# PID.net
KiCad netlist of a schematic drawn in EasyEDA Pro
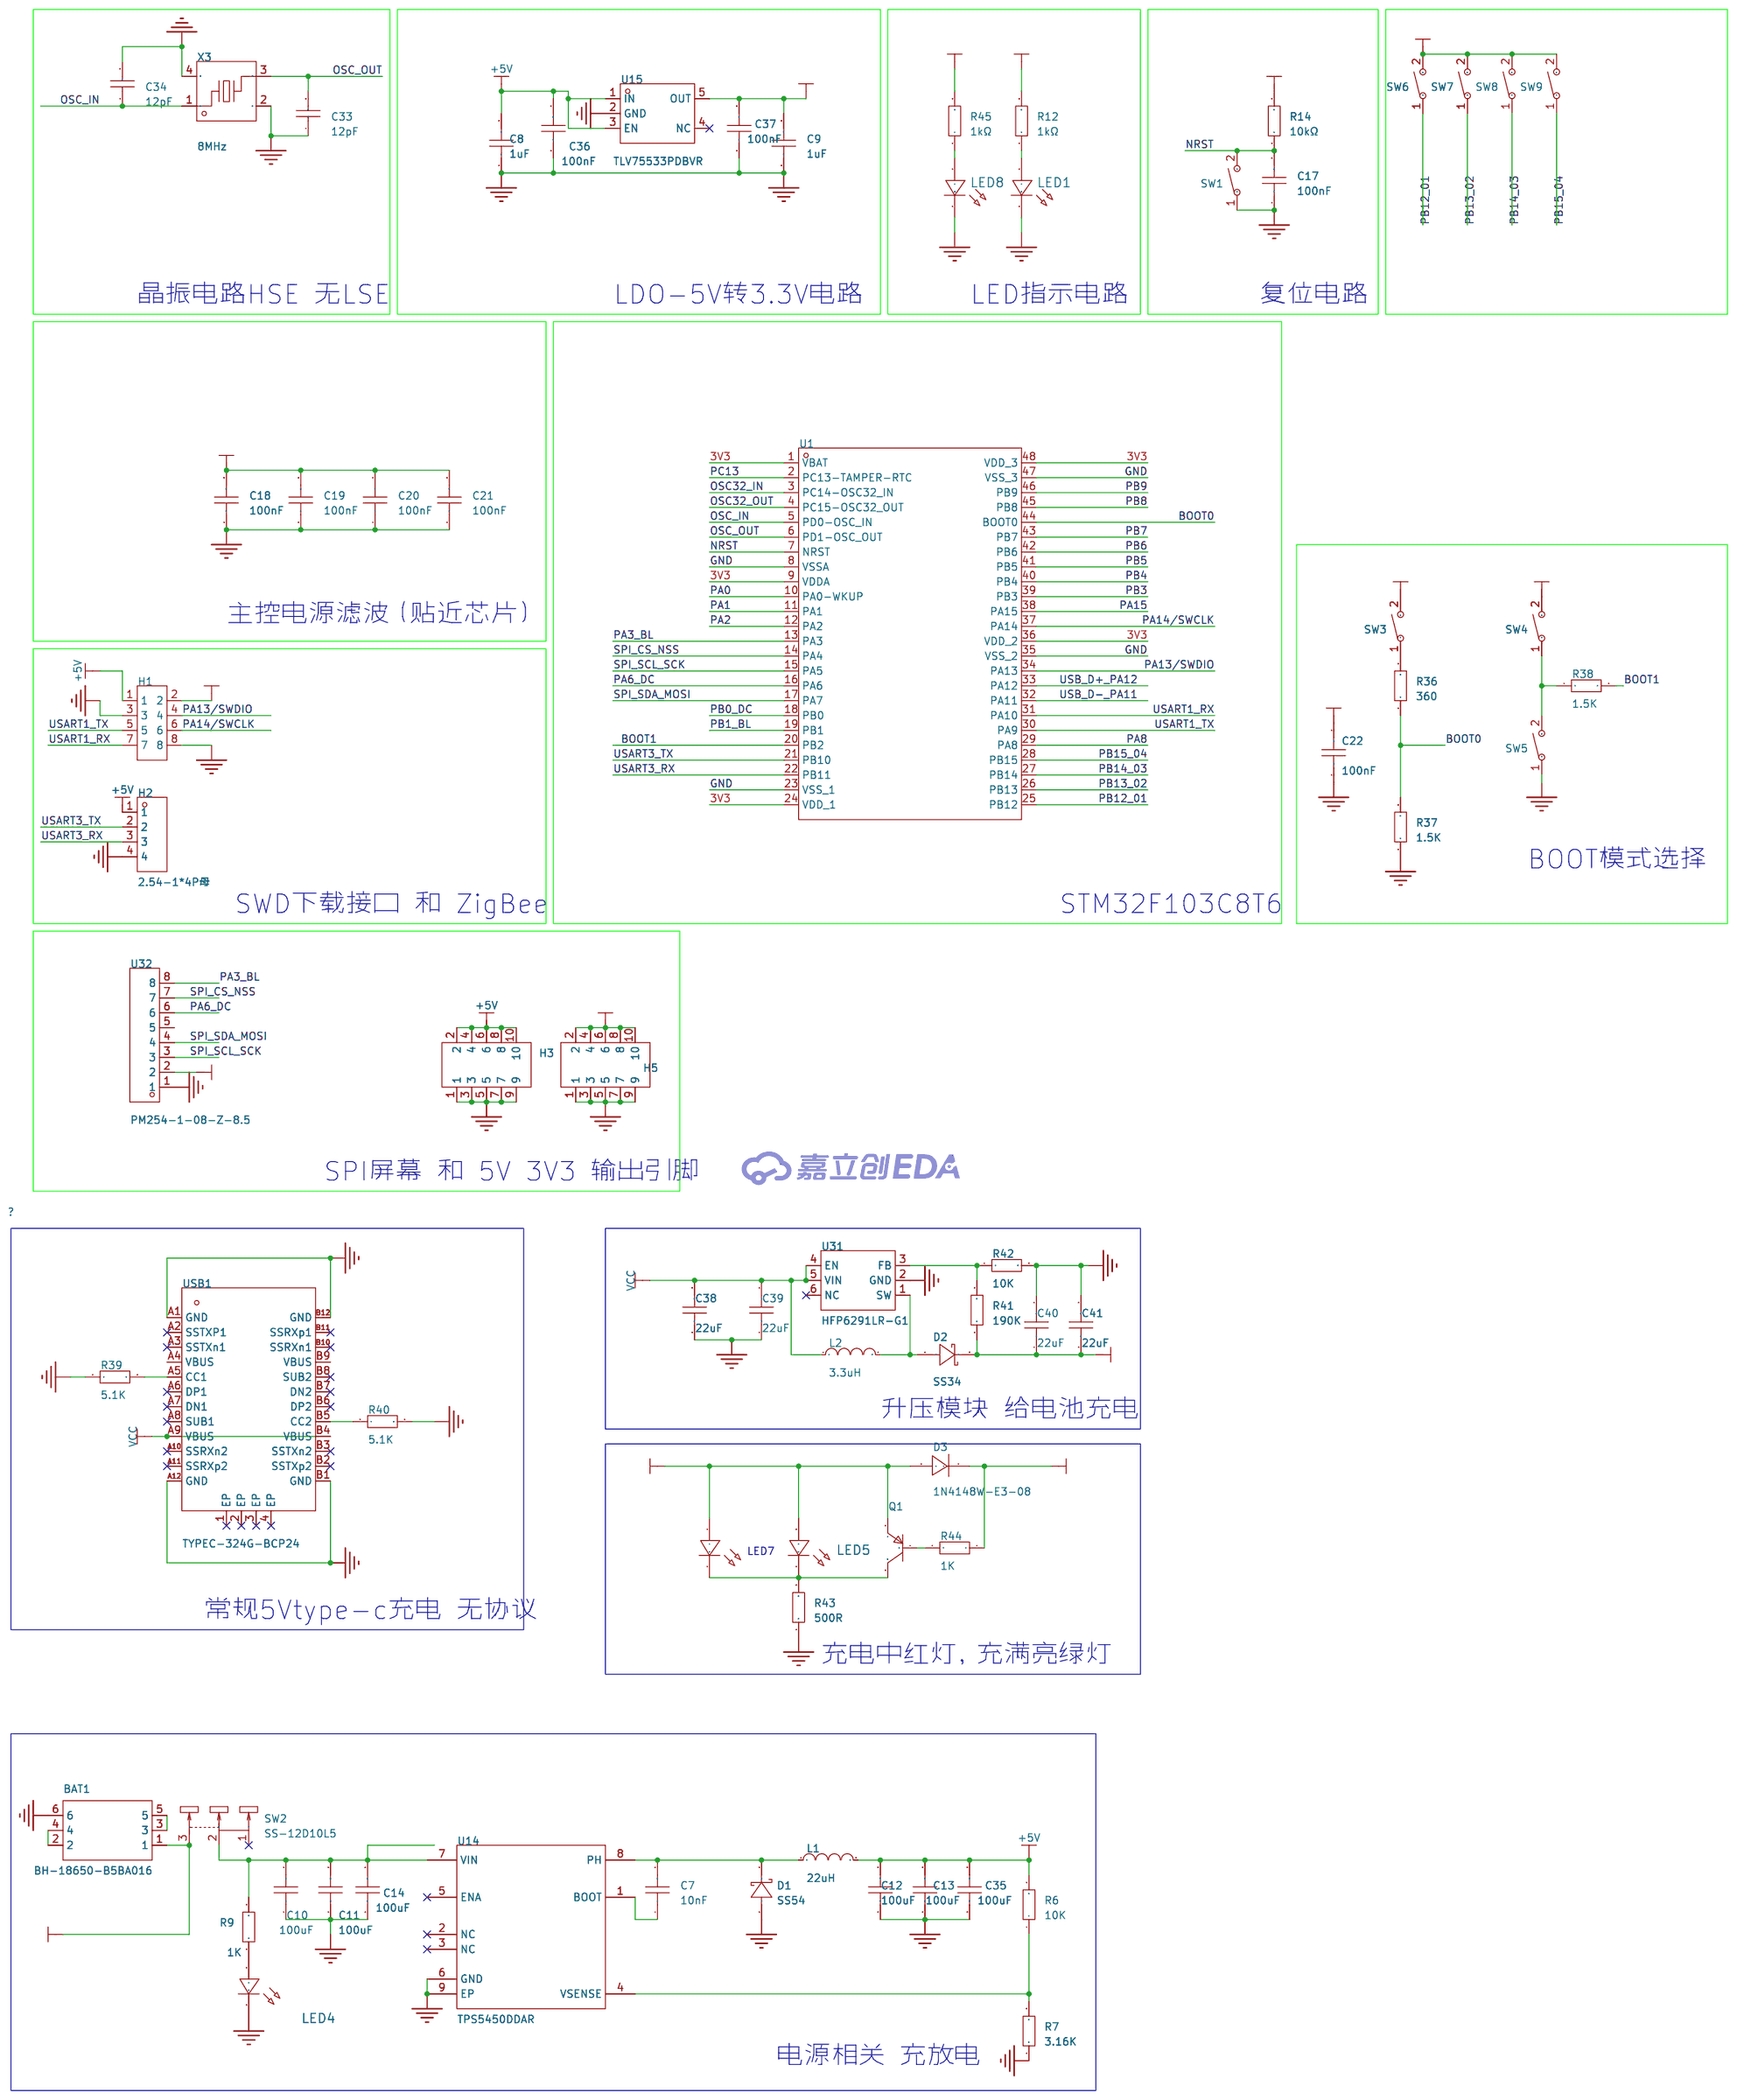
[diagram p0: schematic sheet]

(export (version "E")
  (design (tool "Eeschema 10.0.6"))
  (components
    (comp (ref "BAT1")
      (value "BH-18650-B5BA016")
      (footprint "easyedapro:BAT-SMD_BH-18650-B5BA016")
      (description "连接器类型:电池盒;适用电池规格:-;触点电镀:金;工作温度范围:-25°C~+85°C;")
      (fields (field (name "Manufacturer") "MYOUNG(美阳)"))
      (libsource (lib "easyedapro") (part "BH-18650-B5BA016"))
    )
    (comp (ref "C7")
      (value "100nF")
      (footprint "easyedapro:C0603")
      (libsource (lib "easyedapro") (part "CapAcitance"))
    )
    (comp (ref "C8")
      (value "100nF")
      (footprint "easyedapro:C0603")
      (libsource (lib "easyedapro") (part "CapAcitance"))
    )
    (comp (ref "C9")
      (value "100nF")
      (footprint "easyedapro:C0603")
      (libsource (lib "easyedapro") (part "CapAcitance"))
    )
    (comp (ref "C10")
      (value "100uF")
      (footprint "easyedapro:C1206")
      (description "容值:100uF;精度:±20%;额定电压:10V;材质(温度系数):X5R;")
      (fields
        (field (name "Manufacturer Part") "HGC1206R5107M100NSPJ")
        (field (name "Manufacturer") "Chinocera(华瓷)")
      )
      (libsource (lib "easyedapro") (part "HGC1206R5107M100NSPJ"))
    )
    (comp (ref "C11")
      (value "100uF")
      (footprint "easyedapro:C1206")
      (description "容值:100uF;精度:±20%;额定电压:10V;材质(温度系数):X5R;")
      (fields
        (field (name "Manufacturer Part") "HGC1206R5107M100NSPJ")
        (field (name "Manufacturer") "Chinocera(华瓷)")
      )
      (libsource (lib "easyedapro") (part "HGC1206R5107M100NSPJ"))
    )
    (comp (ref "C12")
      (value "100uF")
      (footprint "easyedapro:C1206")
      (description "容值:100uF;精度:±20%;额定电压:10V;材质(温度系数):X5R;")
      (fields
        (field (name "Manufacturer Part") "HGC1206R5107M100NSPJ")
        (field (name "Manufacturer") "Chinocera(华瓷)")
      )
      (libsource (lib "easyedapro") (part "HGC1206R5107M100NSPJ"))
    )
    (comp (ref "C13")
      (value "100uF")
      (footprint "easyedapro:C1206")
      (description "容值:100uF;精度:±20%;额定电压:10V;材质(温度系数):X5R;")
      (fields
        (field (name "Manufacturer Part") "HGC1206R5107M100NSPJ")
        (field (name "Manufacturer") "Chinocera(华瓷)")
      )
      (libsource (lib "easyedapro") (part "HGC1206R5107M100NSPJ"))
    )
    (comp (ref "C14")
      (value "100uF")
      (footprint "easyedapro:C1206")
      (description "容值:100uF;精度:±20%;额定电压:10V;材质(温度系数):X5R;")
      (fields
        (field (name "Manufacturer Part") "HGC1206R5107M100NSPJ")
        (field (name "Manufacturer") "Chinocera(华瓷)")
      )
      (libsource (lib "easyedapro") (part "HGC1206R5107M100NSPJ"))
    )
    (comp (ref "C17")
      (value "100nF")
      (footprint "easyedapro:C0402")
      (description "容值:100nF;精度:±10%;额定电压:50V;材质(温度系数):X7R;")
      (fields
        (field (name "Manufacturer Part") "GRM155R71H104KE14D")
        (field (name "Manufacturer") "muRata(村田)")
      )
      (libsource (lib "easyedapro") (part "GRM155R71H104KE14D"))
    )
    (comp (ref "C18")
      (value "100nF")
      (footprint "easyedapro:C0402")
      (description "容值:100nF;精度:±10%;额定电压:50V;材质(温度系数):X7R;")
      (fields
        (field (name "Manufacturer Part") "GRM155R71H104KE14D")
        (field (name "Manufacturer") "muRata(村田)")
      )
      (libsource (lib "easyedapro") (part "GRM155R71H104KE14D"))
    )
    (comp (ref "C19")
      (value "100nF")
      (footprint "easyedapro:C0402")
      (description "容值:100nF;精度:±10%;额定电压:50V;材质(温度系数):X7R;")
      (fields
        (field (name "Manufacturer Part") "GRM155R71H104KE14D")
        (field (name "Manufacturer") "muRata(村田)")
      )
      (libsource (lib "easyedapro") (part "GRM155R71H104KE14D"))
    )
    (comp (ref "C20")
      (value "100nF")
      (footprint "easyedapro:C0402")
      (description "容值:100nF;精度:±10%;额定电压:50V;材质(温度系数):X7R;")
      (fields
        (field (name "Manufacturer Part") "GRM155R71H104KE14D")
        (field (name "Manufacturer") "muRata(村田)")
      )
      (libsource (lib "easyedapro") (part "GRM155R71H104KE14D"))
    )
    (comp (ref "C21")
      (value "100nF")
      (footprint "easyedapro:C0402")
      (description "容值:100nF;精度:±10%;额定电压:50V;材质(温度系数):X7R;")
      (fields
        (field (name "Manufacturer Part") "GRM155R71H104KE14D")
        (field (name "Manufacturer") "muRata(村田)")
      )
      (libsource (lib "easyedapro") (part "GRM155R71H104KE14D"))
    )
    (comp (ref "C22")
      (value "100nF")
      (footprint "easyedapro:C0402")
      (description "容值:100nF;精度:±10%;额定电压:50V;材质(温度系数):X7R;")
      (fields
        (field (name "Manufacturer Part") "GRM155R71H104KE14D")
        (field (name "Manufacturer") "muRata(村田)")
      )
      (libsource (lib "easyedapro") (part "GRM155R71H104KE14D"))
    )
    (comp (ref "C33")
      (value "12pF")
      (footprint "easyedapro:C0402")
      (description "容值:12pF;精度:±5%;额定电压:50V;材质(温度系数):C0G;")
      (fields (field (name "Manufacturer Part") "0402CG120J500NT") (field (name "Manufacturer") "FH(风华)"))
      (libsource (lib "easyedapro") (part "0402CG120J500NT"))
    )
    (comp (ref "C34")
      (value "12pF")
      (footprint "easyedapro:C0402")
      (description "容值:12pF;精度:±5%;额定电压:50V;材质(温度系数):C0G;")
      (fields (field (name "Manufacturer Part") "0402CG120J500NT") (field (name "Manufacturer") "FH(风华)"))
      (libsource (lib "easyedapro") (part "0402CG120J500NT"))
    )
    (comp (ref "C35")
      (value "100uF")
      (footprint "easyedapro:C1206")
      (description "容值:100uF;精度:±20%;额定电压:10V;材质(温度系数):X5R;")
      (fields
        (field (name "Manufacturer Part") "HGC1206R5107M100NSPJ")
        (field (name "Manufacturer") "Chinocera(华瓷)")
      )
      (libsource (lib "easyedapro") (part "HGC1206R5107M100NSPJ"))
    )
    (comp (ref "C36")
      (value "100nF")
      (footprint "easyedapro:C0402")
      (description "容值:100nF;精度:±10%;额定电压:50V;材质(温度系数):X7R;")
      (fields
        (field (name "Manufacturer Part") "GRM155R71H104KE14D")
        (field (name "Manufacturer") "muRata(村田)")
      )
      (libsource (lib "easyedapro") (part "GRM155R71H104KE14D"))
    )
    (comp (ref "C37")
      (value "100nF")
      (footprint "easyedapro:C0402")
      (description "容值:100nF;精度:±10%;额定电压:50V;材质(温度系数):X7R;")
      (fields
        (field (name "Manufacturer Part") "GRM155R71H104KE14D")
        (field (name "Manufacturer") "muRata(村田)")
      )
      (libsource (lib "easyedapro") (part "GRM155R71H104KE14D"))
    )
    (comp (ref "C38")
      (value "22uF")
      (footprint "easyedapro:C0603")
      (libsource (lib "easyedapro") (part "CapAcitance"))
    )
    (comp (ref "C39")
      (value "22uF")
      (footprint "easyedapro:C0603")
      (libsource (lib "easyedapro") (part "CapAcitance"))
    )
    (comp (ref "C40")
      (value "22uF")
      (footprint "easyedapro:C0603")
      (libsource (lib "easyedapro") (part "CapAcitance"))
    )
    (comp (ref "C41")
      (value "22uF")
      (footprint "easyedapro:C0603")
      (libsource (lib "easyedapro") (part "CapAcitance"))
    )
    (comp (ref "D1")
      (value "SS54")
      (footprint "easyedapro:SMA_L4.3-W2.6-LS5.0-FD")
      (description "二极管配置:独立式;正向压降(Vf):550mV@5.0A;直流反向耐压(Vr):40V;整流电流:5A;")
      (fields (field (name "Manufacturer") "宏迦橙"))
      (libsource (lib "easyedapro") (part "SS54_C7420369"))
    )
    (comp (ref "D2")
      (value "SS34")
      (footprint "easyedapro:SMA_L4.3-W2.6-LS5.0-FD")
      (description "二极管配置:独立式;正向压降(Vf):550mV@3.0A;直流反向耐压(Vr):40V;整流电流:3A;")
      (fields (field (name "Manufacturer") "宏嘉诚"))
      (libsource (lib "easyedapro") (part "SS34_C7420365"))
    )
    (comp (ref "D3")
      (value "1N4148W-E3-08")
      (footprint "easyedapro:SOD-123_L2.8-W1.8-LS3.7-RD")
      (description "二极管配置:1个独立式;正向压降(Vf):1.2V@100mA;直流反向耐压(Vr):75V;整流电流:150mA;反向恢复时间(Trr):4ns;")
      (fields (field (name "Manufacturer") "VISHAY(威世)"))
      (libsource (lib "easyedapro") (part "1N4148W-E3-08"))
    )
    (comp (ref "H1")
      (value "HX PZ2.54-4x2P ZZ")
      (footprint "easyedapro:HDR-TH_8P-P2.54-V-M-R2-C4-S2.54")
      (fields (field (name "Manufacturer") "hanxia(韩下)"))
      (libsource (lib "easyedapro") (part "HX PZ2.54-4X2P ZZ"))
    )
    (comp (ref "H2")
      (value "2.54-1*4P母")
      (footprint "easyedapro:HDR-TH_4P-P2.54-V-F")
      (fields (field (name "Manufacturer") "BOOMELE(博穆精密)"))
      (libsource (lib "easyedapro") (part "2.54-1*4P母"))
    )
    (comp (ref "H3")
      (value "PZ254V-12-10P")
      (footprint "easyedapro:HDR-TH_10P-P2.54-V-M-R2-C5-S2.54")
      (fields (field (name "Manufacturer") "XFCN(兴飞)"))
      (libsource (lib "easyedapro") (part "PZ254V-12-10P"))
    )
    (comp (ref "H5")
      (value "PZ254V-12-10P")
      (footprint "easyedapro:HDR-TH_10P-P2.54-V-M-R2-C5-S2.54")
      (fields (field (name "Manufacturer") "XFCN(兴飞)"))
      (libsource (lib "easyedapro") (part "PZ254V-12-10P"))
    )
    (comp (ref "L1")
      (value "22uH")
      (footprint "easyedapro:IND-SMD_L7.1-W6.6")
      (description "电感值:22uH;精度:±20%;额定电流:3A;")
      (fields
        (field (name "Manufacturer Part") "YSPI0630A-220M")
        (field (name "Manufacturer") "YJYCOIN(益嘉源)")
      )
      (libsource (lib "easyedapro") (part "YSPI0630A-220M"))
    )
    (comp (ref "L2")
      (value "3.3uH")
      (footprint "easyedapro:IND-SMD_L4.4-W4.2-A")
      (description "电感值:3.3uH;精度:±20%;额定电流:3.3A;饱和电流(Isat):4A;类型:一体成型电感;")
      (fields (field (name "Manufacturer Part") "FXL0420-3R3-M") (field (name "Manufacturer") "cjiang(长江微电)"))
      (libsource (lib "easyedapro") (part "FXL0420-3R3-M"))
    )
    (comp (ref "LED1")
      (value "LTST-C190KSKT")
      (footprint "easyedapro:LED_0603")
      (fields (field (name "Manufacturer") "LITEON(光宝)"))
      (libsource (lib "easyedapro") (part "LED_R"))
    )
    (comp (ref "LED4")
      (value "~")
      (footprint "easyedapro:LED_0603")
      (libsource (lib "easyedapro") (part "LED_R"))
    )
    (comp (ref "LED5")
      (value "~")
      (footprint "easyedapro:LED_0603")
      (libsource (lib "easyedapro") (part "LED_R"))
    )
    (comp (ref "LED7")
      (value "~")
      (footprint "easyedapro:LED_0603")
      (libsource (lib "easyedapro") (part "LED_G"))
    )
    (comp (ref "LED8")
      (value "LTST-C190KSKT")
      (footprint "easyedapro:LED_0603")
      (fields (field (name "Manufacturer") "LITEON(光宝)"))
      (libsource (lib "easyedapro") (part "LED_R"))
    )
    (comp (ref "Q1")
      (value "~")
      (footprint "easyedapro:S8550P_SOT")
      (libsource (lib "easyedapro") (part "PNP"))
    )
    (comp (ref "R6") (value "10K") (footprint "easyedapro:R0603") (libsource (lib "easyedapro") (part "电阻")))
    (comp (ref "R7") (value "10K") (footprint "easyedapro:R0603") (libsource (lib "easyedapro") (part "电阻")))
    (comp (ref "R9") (value "1K") (footprint "easyedapro:R0603") (libsource (lib "easyedapro") (part "电阻")))
    (comp (ref "R12")
      (value "1kΩ")
      (footprint "easyedapro:R0402")
      (description "电阻类型:厚膜电阻;阻值:1kΩ;精度:±1%;功率:62.5mW;最大工作电压:50V;温度系数:±100ppm/°C;")
      (fields
        (field (name "Manufacturer Part") "0402WGF1001TCE")
        (field (name "Manufacturer") "UNI-ROYAL(厚声)")
      )
      (libsource (lib "easyedapro") (part "0402WGF1001TCE"))
    )
    (comp (ref "R14")
      (value "10kΩ")
      (footprint "easyedapro:R0402")
      (description "电阻类型:厚膜电阻;阻值:10kΩ;精度:±1%;功率:62.5mW;最大工作电压:50V;温度系数:±100ppm/°C;")
      (fields (field (name "Manufacturer Part") "RC0402FR-0710KL") (field (name "Manufacturer") "YAGEO(国巨)"))
      (libsource (lib "easyedapro") (part "RC0402FR-0710KL"))
    )
    (comp (ref "R36") (value "360") (footprint "easyedapro:R0603") (libsource (lib "easyedapro") (part "电阻")))
    (comp (ref "R37")
      (value "1.5K")
      (footprint "easyedapro:R0603")
      (libsource (lib "easyedapro") (part "电阻"))
    )
    (comp (ref "R38")
      (value "1.5K")
      (footprint "easyedapro:R0603")
      (libsource (lib "easyedapro") (part "电阻"))
    )
    (comp (ref "R39")
      (value "5.1K")
      (footprint "easyedapro:R0603")
      (libsource (lib "easyedapro") (part "电阻"))
    )
    (comp (ref "R40")
      (value "5.1K")
      (footprint "easyedapro:R0603")
      (libsource (lib "easyedapro") (part "电阻"))
    )
    (comp (ref "R41")
      (value "190K")
      (footprint "easyedapro:R0603")
      (libsource (lib "easyedapro") (part "电阻"))
    )
    (comp (ref "R42") (value "10K") (footprint "easyedapro:R0603") (libsource (lib "easyedapro") (part "电阻")))
    (comp (ref "R43")
      (value "500R")
      (footprint "easyedapro:R0603")
      (libsource (lib "easyedapro") (part "电阻"))
    )
    (comp (ref "R44") (value "1K") (footprint "easyedapro:R0603") (libsource (lib "easyedapro") (part "电阻")))
    (comp (ref "R45")
      (value "1kΩ")
      (footprint "easyedapro:R0402")
      (description "电阻类型:厚膜电阻;阻值:1kΩ;精度:±1%;功率:62.5mW;最大工作电压:50V;温度系数:±100ppm/°C;")
      (fields
        (field (name "Manufacturer Part") "0402WGF1001TCE")
        (field (name "Manufacturer") "UNI-ROYAL(厚声)")
      )
      (libsource (lib "easyedapro") (part "0402WGF1001TCE"))
    )
    (comp (ref "SW1")
      (value "TS-1101-B-W")
      (footprint "easyedapro:KEY-SMD_2P-L6.0-W3.6-P7.4-LS8.0-L")
      (description "触点电流:50mA;额定电压(DC):12V;绝缘电阻:-;电路结构:单刀单掷;安装方式:立贴;带灯:无;作用力:160gf;机械寿命:5万次;带支架:否;")
      (fields (field (name "Manufacturer") "XKB Connectivity(中国星坤)"))
      (libsource (lib "easyedapro") (part "TS-1101-B-W"))
    )
    (comp (ref "SW2")
      (value "SS-12D10L5")
      (footprint "easyedapro:SW-TH_SS-12D10L5")
      (description "电路结构:单刀双掷;安装方式:直插;开关颜色:黑色;额定电流(DC):3A;额定电压(DC):125V;额定电流(AC):3A;额定电压(AC):125V;机械寿命:1万次;")
      (fields (field (name "Manufacturer") "XKB Connectivity(中国星坤)"))
      (libsource (lib "easyedapro") (part "SS-12D10L5"))
    )
    (comp (ref "SW3")
      (value "TS-1101-B-W")
      (footprint "easyedapro:KEY-SMD_2P-L6.0-W3.6-P7.4-LS8.0-L")
      (description "触点电流:50mA;额定电压(DC):12V;绝缘电阻:-;电路结构:单刀单掷;安装方式:立贴;带灯:无;作用力:160gf;机械寿命:5万次;带支架:否;")
      (fields (field (name "Manufacturer") "XKB Connectivity(中国星坤)"))
      (libsource (lib "easyedapro") (part "TS-1101-B-W"))
    )
    (comp (ref "SW4")
      (value "TS-1101-B-W")
      (footprint "easyedapro:KEY-SMD_2P-L6.0-W3.6-P7.4-LS8.0-L")
      (description "触点电流:50mA;额定电压(DC):12V;绝缘电阻:-;电路结构:单刀单掷;安装方式:立贴;带灯:无;作用力:160gf;机械寿命:5万次;带支架:否;")
      (fields (field (name "Manufacturer") "XKB Connectivity(中国星坤)"))
      (libsource (lib "easyedapro") (part "TS-1101-B-W"))
    )
    (comp (ref "SW5")
      (value "TS-1101-B-W")
      (footprint "easyedapro:KEY-SMD_2P-L6.0-W3.6-P7.4-LS8.0-L")
      (description "触点电流:50mA;额定电压(DC):12V;绝缘电阻:-;电路结构:单刀单掷;安装方式:立贴;带灯:无;作用力:160gf;机械寿命:5万次;带支架:否;")
      (fields (field (name "Manufacturer") "XKB Connectivity(中国星坤)"))
      (libsource (lib "easyedapro") (part "TS-1101-B-W"))
    )
    (comp (ref "SW6")
      (value "TS-1101-B-W")
      (footprint "easyedapro:KEY-SMD_2P-L6.0-W3.6-P7.4-LS8.0-L")
      (description "触点电流:50mA;额定电压(DC):12V;绝缘电阻:-;电路结构:单刀单掷;安装方式:立贴;带灯:无;作用力:160gf;机械寿命:5万次;带支架:否;")
      (fields (field (name "Manufacturer") "XKB Connectivity(中国星坤)"))
      (libsource (lib "easyedapro") (part "TS-1101-B-W"))
    )
    (comp (ref "SW7")
      (value "TS-1101-B-W")
      (footprint "easyedapro:KEY-SMD_2P-L6.0-W3.6-P7.4-LS8.0-L")
      (description "触点电流:50mA;额定电压(DC):12V;绝缘电阻:-;电路结构:单刀单掷;安装方式:立贴;带灯:无;作用力:160gf;机械寿命:5万次;带支架:否;")
      (fields (field (name "Manufacturer") "XKB Connectivity(中国星坤)"))
      (libsource (lib "easyedapro") (part "TS-1101-B-W"))
    )
    (comp (ref "SW8")
      (value "TS-1101-B-W")
      (footprint "easyedapro:KEY-SMD_2P-L6.0-W3.6-P7.4-LS8.0-L")
      (description "触点电流:50mA;额定电压(DC):12V;绝缘电阻:-;电路结构:单刀单掷;安装方式:立贴;带灯:无;作用力:160gf;机械寿命:5万次;带支架:否;")
      (fields (field (name "Manufacturer") "XKB Connectivity(中国星坤)"))
      (libsource (lib "easyedapro") (part "TS-1101-B-W"))
    )
    (comp (ref "SW9")
      (value "TS-1101-B-W")
      (footprint "easyedapro:KEY-SMD_2P-L6.0-W3.6-P7.4-LS8.0-L")
      (description "触点电流:50mA;额定电压(DC):12V;绝缘电阻:-;电路结构:单刀单掷;安装方式:立贴;带灯:无;作用力:160gf;机械寿命:5万次;带支架:否;")
      (fields (field (name "Manufacturer") "XKB Connectivity(中国星坤)"))
      (libsource (lib "easyedapro") (part "TS-1101-B-W"))
    )
    (comp (ref "U1")
      (value "STM32F103C8T6")
      (footprint "easyedapro:LQFP-48_L7.0-W7.0-P0.50-LS9.0-BL")
      (description "CPU内核:CM3;程序存储容量:64KB;RAM总容量:20KB;GPIO端口数量:37;工作电压范围:2V~3.6V;CPU最大主频:72MHz;程序存储器类型:FLASH;")
      (fields (field (name "Manufacturer") "ST(意法半导体)"))
      (libsource (lib "easyedapro") (part "STM32F103C8T6"))
    )
    (comp (ref "U14")
      (value "TPS5450DDAR")
      (footprint "easyedapro:SOP-8_L4.9-W3.9-P1.27-LS6.0-BL-EP")
      (description "功能类型:降压型;输出类型:可调;工作电压:5.5V~36V;输出电压:1.221V~31.32V;输出电流:5A;")
      (fields (field (name "Manufacturer") "TI(德州仪器)"))
      (libsource (lib "easyedapro") (part "TPS5450DDAR"))
    )
    (comp (ref "U15")
      (value "TLV75533PDBVR")
      (footprint "easyedapro:SOT-23-5_L3.0-W1.7-P0.95-LS2.8-BR")
      (description "输出类型:固定;最大输入电压:5.5V;输出电压:3.3V;输出电流:500mA;电源纹波抑制比(PSRR):52dB;输出极性:正极;")
      (fields (field (name "Manufacturer") "TI(德州仪器)"))
      (libsource (lib "easyedapro") (part "TLV75533PDBVR"))
    )
    (comp (ref "U31")
      (value "HFP6291LR-G1")
      (footprint "easyedapro:SOT-23-6_L2.9-W1.6-P0.95-LS2.8-BR")
      (description "功能类型:升压型;输出类型:-;工作电压:2V~24V;输出电压:-;输出电流:-;")
      (fields (field (name "Manufacturer") "HXY MOSFET(华轩阳电子)"))
      (libsource (lib "easyedapro") (part "HFP6291LR-G1"))
    )
    (comp (ref "U32")
      (value "PM254-1-08-Z-8.5")
      (footprint "easyedapro:HDR-TH_8P-P2.54-V-F")
      (fields (field (name "Manufacturer") "HCTL(华灿天禄)"))
      (libsource (lib "easyedapro") (part "PM254-1-08-Z-8.5"))
    )
    (comp (ref "USB1")
      (value "TYPEC-324G-BCP24")
      (footprint "easyedapro:USB-C-SMD_TYPEC-324G-BCP24")
      (description "连接器类型:Type-C;标准:USB 3.1;公母:母;安装方式:卧贴;触点数量:24P;端口数量:1;额定电流 - 电源:5A;工作温度范围:-45°C~+85°C;")
      (fields (field (name "Manufacturer") "XUNPU(讯普)"))
      (libsource (lib "easyedapro") (part "TYPEC-324G-BCP24"))
    )
    (comp (ref "X3")
      (value "8MHz")
      (footprint "easyedapro:CRYSTAL-SMD_4P-L3.2-W2.5-BL-1")
      (description "晶振类型:贴片晶振;频率:8MHz;常温频差:±10ppm;外接负载电容:12pF;频率稳定度(全温):±20ppm;")
      (fields
        (field (name "Manufacturer Part") "XL2EL89COI-111YLC-8M")
        (field (name "Manufacturer") "YXC(扬兴晶振)")
      )
      (libsource (lib "easyedapro") (part "XL2EL89COI-111YLC-8M"))
    )
  )
  (nets
    (net (code "1") (name "+5V") (class "Default")
      (node (ref "C12") (pin "2") (pinfunction "2_2") (pintype "unspecified"))
      (node (ref "C13") (pin "2") (pinfunction "2_2") (pintype "unspecified"))
      (node (ref "C35") (pin "2") (pinfunction "2_2") (pintype "unspecified"))
      (node (ref "C36") (pin "2") (pinfunction "2_2") (pintype "unspecified"))
      (node (ref "C8") (pin "2") (pinfunction "2_2") (pintype "input"))
      (node (ref "H1") (pin "1") (pinfunction "1_1") (pintype "unspecified"))
      (node (ref "H2") (pin "1") (pinfunction "1_1") (pintype "unspecified"))
      (node (ref "H3") (pin "10") (pinfunction "10_10") (pintype "unspecified"))
      (node (ref "H3") (pin "2") (pinfunction "2_2") (pintype "unspecified"))
      (node (ref "H3") (pin "4") (pinfunction "4_4") (pintype "unspecified"))
      (node (ref "H3") (pin "6") (pinfunction "6_6") (pintype "unspecified"))
      (node (ref "H3") (pin "8") (pinfunction "8_8") (pintype "unspecified"))
      (node (ref "L1") (pin "2") (pinfunction "2_2") (pintype "unspecified"))
      (node (ref "R45") (pin "2") (pinfunction "2_2") (pintype "input"))
      (node (ref "R6") (pin "2") (pinfunction "2_2") (pintype "input"))
      (node (ref "U15") (pin "1") (pinfunction "IN_1") (pintype "unspecified"))
      (node (ref "U15") (pin "3") (pinfunction "EN_3") (pintype "unspecified"))
    )
    (net (code "2") (name "+12V") (class "Default")
      (node (ref "C40") (pin "1") (pinfunction "1_1") (pintype "input"))
      (node (ref "C41") (pin "1") (pinfunction "1_1") (pintype "input"))
      (node (ref "D2") (pin "2") (pinfunction "K_2") (pintype "unspecified"))
      (node (ref "D3") (pin "2") (pinfunction "A_2") (pintype "unspecified"))
      (node (ref "LED5") (pin "2") (pinfunction "A_2") (pintype "input"))
      (node (ref "LED7") (pin "2") (pinfunction "A_2") (pintype "input"))
      (node (ref "Q1") (pin "2") (pinfunction "E_2") (pintype "input"))
      (node (ref "R41") (pin "1") (pinfunction "1_1") (pintype "input"))
    )
    (net (code "3") (name "/BOOT0") (class "Default")
      (node (ref "R36") (pin "1") (pinfunction "1_1") (pintype "input"))
      (node (ref "R37") (pin "2") (pinfunction "2_2") (pintype "input"))
      (node (ref "U1") (pin "44") (pinfunction "BOOT0_44") (pintype "unspecified"))
    )
    (net (code "4") (name "/BOOT1") (class "Default")
      (node (ref "R38") (pin "2") (pinfunction "2_2") (pintype "input"))
      (node (ref "U1") (pin "20") (pinfunction "PB2_20") (pintype "unspecified"))
    )
    (net (code "5") (name "/NRST") (class "Default")
      (node (ref "C17") (pin "2") (pinfunction "2_2") (pintype "unspecified"))
      (node (ref "R14") (pin "1") (pinfunction "1_1") (pintype "input"))
      (node (ref "SW1") (pin "2") (pinfunction "2_2") (pintype "input"))
      (node (ref "U1") (pin "7") (pinfunction "NRST_7") (pintype "unspecified"))
    )
    (net (code "6") (name "/OSC32_IN") (class "Default")
      (node (ref "U1") (pin "3") (pinfunction "PC14-OSC32_IN_3") (pintype "unspecified"))
    )
    (net (code "7") (name "/OSC32_OUT") (class "Default")
      (node (ref "U1") (pin "4") (pinfunction "PC15-OSC32_OUT_4") (pintype "unspecified"))
    )
    (net (code "8") (name "/OSC_IN") (class "Default")
      (node (ref "C34") (pin "1") (pinfunction "1_1") (pintype "input"))
      (node (ref "U1") (pin "5") (pinfunction "PD0-OSC_IN_5") (pintype "unspecified"))
      (node (ref "X3") (pin "1") (pinfunction "1_1") (pintype "input"))
    )
    (net (code "9") (name "/OSC_OUT") (class "Default")
      (node (ref "C33") (pin "2") (pinfunction "2_2") (pintype "input"))
      (node (ref "U1") (pin "6") (pinfunction "PD1-OSC_OUT_6") (pintype "unspecified"))
      (node (ref "X3") (pin "3") (pinfunction "3_3") (pintype "input"))
    )
    (net (code "10") (name "/PA0") (class "Default")
      (node (ref "U1") (pin "10") (pinfunction "PA0-WKUP_10") (pintype "unspecified"))
    )
    (net (code "11") (name "/PA1") (class "Default")
      (node (ref "U1") (pin "11") (pinfunction "PA1_11") (pintype "unspecified"))
    )
    (net (code "12") (name "/PA2") (class "Default")
      (node (ref "U1") (pin "12") (pinfunction "PA2_12") (pintype "unspecified"))
    )
    (net (code "13") (name "/PA3_BL") (class "Default")
      (node (ref "U1") (pin "13") (pinfunction "PA3_13") (pintype "unspecified"))
      (node (ref "U32") (pin "8") (pinfunction "8_8") (pintype "unspecified"))
    )
    (net (code "14") (name "/PA6_DC") (class "Default")
      (node (ref "U1") (pin "16") (pinfunction "PA6_16") (pintype "unspecified"))
      (node (ref "U32") (pin "6") (pinfunction "6_6") (pintype "unspecified"))
    )
    (net (code "15") (name "/PA8") (class "Default")
      (node (ref "U1") (pin "29") (pinfunction "PA8_29") (pintype "unspecified"))
    )
    (net (code "16") (name "/PA13{slash}SWDIO") (class "Default")
      (node (ref "H1") (pin "4") (pinfunction "4_4") (pintype "unspecified"))
      (node (ref "U1") (pin "34") (pinfunction "PA13_34") (pintype "unspecified"))
    )
    (net (code "17") (name "/PA14{slash}SWCLK") (class "Default")
      (node (ref "H1") (pin "6") (pinfunction "6_6") (pintype "unspecified"))
      (node (ref "U1") (pin "37") (pinfunction "PA14_37") (pintype "unspecified"))
    )
    (net (code "18") (name "/PA15") (class "Default")
      (node (ref "U1") (pin "38") (pinfunction "PA15_38") (pintype "unspecified"))
    )
    (net (code "19") (name "/PB0_DC") (class "Default")
      (node (ref "U1") (pin "18") (pinfunction "PB0_18") (pintype "unspecified"))
    )
    (net (code "20") (name "/PB1_BL") (class "Default")
      (node (ref "U1") (pin "19") (pinfunction "PB1_19") (pintype "unspecified"))
    )
    (net (code "21") (name "/PB3") (class "Default")
      (node (ref "U1") (pin "39") (pinfunction "PB3_39") (pintype "unspecified"))
    )
    (net (code "22") (name "/PB4") (class "Default")
      (node (ref "U1") (pin "40") (pinfunction "PB4_40") (pintype "unspecified"))
    )
    (net (code "23") (name "/PB5") (class "Default")
      (node (ref "U1") (pin "41") (pinfunction "PB5_41") (pintype "unspecified"))
    )
    (net (code "24") (name "/PB6") (class "Default")
      (node (ref "U1") (pin "42") (pinfunction "PB6_42") (pintype "unspecified"))
    )
    (net (code "25") (name "/PB7") (class "Default")
      (node (ref "U1") (pin "43") (pinfunction "PB7_43") (pintype "unspecified"))
    )
    (net (code "26") (name "/PB8") (class "Default")
      (node (ref "U1") (pin "45") (pinfunction "PB8_45") (pintype "unspecified"))
    )
    (net (code "27") (name "/PB9") (class "Default")
      (node (ref "U1") (pin "46") (pinfunction "PB9_46") (pintype "unspecified"))
    )
    (net (code "28") (name "/PB12_01") (class "Default")
      (node (ref "SW6") (pin "1") (pinfunction "1_1") (pintype "input"))
      (node (ref "U1") (pin "25") (pinfunction "PB12_25") (pintype "unspecified"))
    )
    (net (code "29") (name "/PB13_02") (class "Default")
      (node (ref "SW7") (pin "1") (pinfunction "1_1") (pintype "input"))
      (node (ref "U1") (pin "26") (pinfunction "PB13_26") (pintype "unspecified"))
    )
    (net (code "30") (name "/PB14_03") (class "Default")
      (node (ref "SW8") (pin "1") (pinfunction "1_1") (pintype "input"))
      (node (ref "U1") (pin "27") (pinfunction "PB14_27") (pintype "unspecified"))
    )
    (net (code "31") (name "/PB15_04") (class "Default")
      (node (ref "SW9") (pin "1") (pinfunction "1_1") (pintype "input"))
      (node (ref "U1") (pin "28") (pinfunction "PB15_28") (pintype "unspecified"))
    )
    (net (code "32") (name "/PC13") (class "Default")
      (node (ref "U1") (pin "2") (pinfunction "PC13-TAMPER-RTC_2") (pintype "unspecified"))
    )
    (net (code "33") (name "/SPI_CS_NSS") (class "Default")
      (node (ref "U1") (pin "14") (pinfunction "PA4_14") (pintype "unspecified"))
      (node (ref "U32") (pin "7") (pinfunction "7_7") (pintype "unspecified"))
    )
    (net (code "34") (name "/SPI_SCL_SCK") (class "Default")
      (node (ref "U1") (pin "15") (pinfunction "PA5_15") (pintype "unspecified"))
      (node (ref "U32") (pin "3") (pinfunction "3_3") (pintype "unspecified"))
    )
    (net (code "35") (name "/SPI_SDA_MOSI") (class "Default")
      (node (ref "U1") (pin "17") (pinfunction "PA7_17") (pintype "unspecified"))
      (node (ref "U32") (pin "4") (pinfunction "4_4") (pintype "unspecified"))
    )
    (net (code "36") (name "/USART1_RX") (class "Default")
      (node (ref "H1") (pin "7") (pinfunction "7_7") (pintype "unspecified"))
      (node (ref "U1") (pin "31") (pinfunction "PA10_31") (pintype "unspecified"))
    )
    (net (code "37") (name "/USART1_TX") (class "Default")
      (node (ref "H1") (pin "5") (pinfunction "5_5") (pintype "unspecified"))
      (node (ref "U1") (pin "30") (pinfunction "PA9_30") (pintype "unspecified"))
    )
    (net (code "38") (name "/USART3_RX") (class "Default")
      (node (ref "H2") (pin "3") (pinfunction "3_3") (pintype "unspecified"))
      (node (ref "U1") (pin "22") (pinfunction "PB11_22") (pintype "unspecified"))
    )
    (net (code "39") (name "/USART3_TX") (class "Default")
      (node (ref "H2") (pin "2") (pinfunction "2_2") (pintype "unspecified"))
      (node (ref "U1") (pin "21") (pinfunction "PB10_21") (pintype "unspecified"))
    )
    (net (code "40") (name "/USB_D+_PA12") (class "Default")
      (node (ref "U1") (pin "33") (pinfunction "PA12_33") (pintype "unspecified"))
    )
    (net (code "41") (name "/USB_D-_PA11") (class "Default")
      (node (ref "U1") (pin "32") (pinfunction "PA11_32") (pintype "unspecified"))
    )
    (net (code "42") (name "3V3") (class "Default")
      (node (ref "C18") (pin "2") (pinfunction "2_2") (pintype "unspecified"))
      (node (ref "C19") (pin "2") (pinfunction "2_2") (pintype "unspecified"))
      (node (ref "C20") (pin "2") (pinfunction "2_2") (pintype "unspecified"))
      (node (ref "C21") (pin "2") (pinfunction "2_2") (pintype "unspecified"))
      (node (ref "C22") (pin "2") (pinfunction "2_2") (pintype "unspecified"))
      (node (ref "C37") (pin "2") (pinfunction "2_2") (pintype "unspecified"))
      (node (ref "C9") (pin "2") (pinfunction "2_2") (pintype "input"))
      (node (ref "H1") (pin "2") (pinfunction "2_2") (pintype "unspecified"))
      (node (ref "H5") (pin "10") (pinfunction "10_10") (pintype "unspecified"))
      (node (ref "H5") (pin "2") (pinfunction "2_2") (pintype "unspecified"))
      (node (ref "H5") (pin "4") (pinfunction "4_4") (pintype "unspecified"))
      (node (ref "H5") (pin "6") (pinfunction "6_6") (pintype "unspecified"))
      (node (ref "H5") (pin "8") (pinfunction "8_8") (pintype "unspecified"))
      (node (ref "R12") (pin "2") (pinfunction "2_2") (pintype "input"))
      (node (ref "R14") (pin "2") (pinfunction "2_2") (pintype "input"))
      (node (ref "SW3") (pin "2") (pinfunction "2_2") (pintype "input"))
      (node (ref "SW4") (pin "2") (pinfunction "2_2") (pintype "input"))
      (node (ref "SW6") (pin "2") (pinfunction "2_2") (pintype "input"))
      (node (ref "SW7") (pin "2") (pinfunction "2_2") (pintype "input"))
      (node (ref "SW8") (pin "2") (pinfunction "2_2") (pintype "input"))
      (node (ref "SW9") (pin "2") (pinfunction "2_2") (pintype "input"))
      (node (ref "U1") (pin "1") (pinfunction "VBAT_1") (pintype "unspecified"))
      (node (ref "U1") (pin "24") (pinfunction "VDD_1_24") (pintype "unspecified"))
      (node (ref "U1") (pin "36") (pinfunction "VDD_2_36") (pintype "unspecified"))
      (node (ref "U1") (pin "48") (pinfunction "VDD_3_48") (pintype "unspecified"))
      (node (ref "U1") (pin "9") (pinfunction "VDDA_9") (pintype "unspecified"))
      (node (ref "U15") (pin "5") (pinfunction "OUT_5") (pintype "unspecified"))
      (node (ref "U32") (pin "2") (pinfunction "2_2") (pintype "unspecified"))
    )
    (net (code "43") (name "GND") (class "Default")
      (node (ref "BAT1") (pin "6") (pinfunction "6_6") (pintype "unspecified"))
      (node (ref "C10") (pin "1") (pinfunction "1_1") (pintype "unspecified"))
      (node (ref "C11") (pin "1") (pinfunction "1_1") (pintype "unspecified"))
      (node (ref "C12") (pin "1") (pinfunction "1_1") (pintype "unspecified"))
      (node (ref "C13") (pin "1") (pinfunction "1_1") (pintype "unspecified"))
      (node (ref "C14") (pin "1") (pinfunction "1_1") (pintype "unspecified"))
      (node (ref "C17") (pin "1") (pinfunction "1_1") (pintype "unspecified"))
      (node (ref "C18") (pin "1") (pinfunction "1_1") (pintype "unspecified"))
      (node (ref "C19") (pin "1") (pinfunction "1_1") (pintype "unspecified"))
      (node (ref "C20") (pin "1") (pinfunction "1_1") (pintype "unspecified"))
      (node (ref "C21") (pin "1") (pinfunction "1_1") (pintype "unspecified"))
      (node (ref "C22") (pin "1") (pinfunction "1_1") (pintype "unspecified"))
      (node (ref "C33") (pin "1") (pinfunction "1_1") (pintype "input"))
      (node (ref "C34") (pin "2") (pinfunction "2_2") (pintype "input"))
      (node (ref "C35") (pin "1") (pinfunction "1_1") (pintype "unspecified"))
      (node (ref "C36") (pin "1") (pinfunction "1_1") (pintype "unspecified"))
      (node (ref "C37") (pin "1") (pinfunction "1_1") (pintype "unspecified"))
      (node (ref "C38") (pin "1") (pinfunction "1_1") (pintype "input"))
      (node (ref "C39") (pin "1") (pinfunction "1_1") (pintype "input"))
      (node (ref "C40") (pin "2") (pinfunction "2_2") (pintype "input"))
      (node (ref "C41") (pin "2") (pinfunction "2_2") (pintype "input"))
      (node (ref "C8") (pin "1") (pinfunction "1_1") (pintype "input"))
      (node (ref "C9") (pin "1") (pinfunction "1_1") (pintype "input"))
      (node (ref "D1") (pin "1") (pinfunction "A_1") (pintype "unspecified"))
      (node (ref "H1") (pin "3") (pinfunction "3_3") (pintype "unspecified"))
      (node (ref "H1") (pin "8") (pinfunction "8_8") (pintype "unspecified"))
      (node (ref "H2") (pin "4") (pinfunction "4_4") (pintype "unspecified"))
      (node (ref "H3") (pin "1") (pinfunction "1_1") (pintype "unspecified"))
      (node (ref "H3") (pin "3") (pinfunction "3_3") (pintype "unspecified"))
      (node (ref "H3") (pin "5") (pinfunction "5_5") (pintype "unspecified"))
      (node (ref "H3") (pin "7") (pinfunction "7_7") (pintype "unspecified"))
      (node (ref "H3") (pin "9") (pinfunction "9_9") (pintype "unspecified"))
      (node (ref "H5") (pin "1") (pinfunction "1_1") (pintype "unspecified"))
      (node (ref "H5") (pin "3") (pinfunction "3_3") (pintype "unspecified"))
      (node (ref "H5") (pin "5") (pinfunction "5_5") (pintype "unspecified"))
      (node (ref "H5") (pin "7") (pinfunction "7_7") (pintype "unspecified"))
      (node (ref "H5") (pin "9") (pinfunction "9_9") (pintype "unspecified"))
      (node (ref "LED1") (pin "1") (pinfunction "C_1") (pintype "input"))
      (node (ref "LED4") (pin "1") (pinfunction "C_1") (pintype "input"))
      (node (ref "LED8") (pin "1") (pinfunction "C_1") (pintype "input"))
      (node (ref "R37") (pin "1") (pinfunction "1_1") (pintype "input"))
      (node (ref "R39") (pin "1") (pinfunction "1_1") (pintype "input"))
      (node (ref "R40") (pin "2") (pinfunction "2_2") (pintype "input"))
      (node (ref "R42") (pin "2") (pinfunction "2_2") (pintype "input"))
      (node (ref "R43") (pin "1") (pinfunction "1_1") (pintype "input"))
      (node (ref "R7") (pin "1") (pinfunction "1_1") (pintype "input"))
      (node (ref "SW1") (pin "1") (pinfunction "1_1") (pintype "input"))
      (node (ref "SW5") (pin "1") (pinfunction "1_1") (pintype "input"))
      (node (ref "U1") (pin "23") (pinfunction "VSS_1_23") (pintype "unspecified"))
      (node (ref "U1") (pin "35") (pinfunction "VSS_2_35") (pintype "unspecified"))
      (node (ref "U1") (pin "47") (pinfunction "VSS_3_47") (pintype "unspecified"))
      (node (ref "U1") (pin "8") (pinfunction "VSSA_8") (pintype "unspecified"))
      (node (ref "U14") (pin "6") (pinfunction "GND_6") (pintype "unspecified"))
      (node (ref "U14") (pin "9") (pinfunction "EP_9") (pintype "unspecified"))
      (node (ref "U15") (pin "2") (pinfunction "GND_2") (pintype "unspecified"))
      (node (ref "U31") (pin "2") (pinfunction "GND_2") (pintype "unspecified"))
      (node (ref "U32") (pin "1") (pinfunction "1_1") (pintype "unspecified"))
      (node (ref "USB1") (pin "A1") (pinfunction "GND_A1") (pintype "unspecified"))
      (node (ref "USB1") (pin "A12") (pinfunction "GND_A12") (pintype "unspecified"))
      (node (ref "USB1") (pin "B1") (pinfunction "GND_B1") (pintype "unspecified"))
      (node (ref "USB1") (pin "B12") (pinfunction "GND_B12") (pintype "unspecified"))
      (node (ref "X3") (pin "2") (pinfunction "GND_2") (pintype "input"))
      (node (ref "X3") (pin "4") (pinfunction "GND_4") (pintype "input"))
    )
    (net (code "44") (name "Net-(BAT1-Pad2)") (class "Default")
      (node (ref "BAT1") (pin "2") (pinfunction "2_2") (pintype "unspecified"))
      (node (ref "BAT1") (pin "4") (pinfunction "4_4") (pintype "unspecified"))
    )
    (net (code "45") (name "Net-(BAT1-Pad3)") (class "Default")
      (node (ref "BAT1") (pin "3") (pinfunction "3_3") (pintype "unspecified"))
      (node (ref "BAT1") (pin "5") (pinfunction "5_5") (pintype "unspecified"))
    )
    (net (code "46") (name "Net-(D1-K)") (class "Default")
      (node (ref "C7") (pin "2") (pinfunction "2_2") (pintype "input"))
      (node (ref "D1") (pin "2") (pinfunction "K_2") (pintype "unspecified"))
      (node (ref "L1") (pin "1") (pinfunction "1_1") (pintype "unspecified"))
      (node (ref "U14") (pin "8") (pinfunction "PH_8") (pintype "output"))
    )
    (net (code "47") (name "Net-(D2-A)") (class "Default")
      (node (ref "D2") (pin "1") (pinfunction "A_1") (pintype "unspecified"))
      (node (ref "L2") (pin "2") (pinfunction "2_2") (pintype "unspecified"))
      (node (ref "U31") (pin "1") (pinfunction "SW_1") (pintype "unspecified"))
    )
    (net (code "48") (name "Net-(LED1-A)") (class "Default")
      (node (ref "LED1") (pin "2") (pinfunction "A_2") (pintype "input"))
      (node (ref "R12") (pin "1") (pinfunction "1_1") (pintype "input"))
    )
    (net (code "49") (name "Net-(LED4-A)") (class "Default")
      (node (ref "LED4") (pin "2") (pinfunction "A_2") (pintype "input"))
      (node (ref "R9") (pin "1") (pinfunction "1_1") (pintype "input"))
    )
    (net (code "50") (name "Net-(LED5-C)") (class "Default")
      (node (ref "LED5") (pin "1") (pinfunction "C_1") (pintype "input"))
      (node (ref "LED7") (pin "1") (pinfunction "C_1") (pintype "input"))
      (node (ref "Q1") (pin "3") (pinfunction "C_3") (pintype "input"))
      (node (ref "R43") (pin "2") (pinfunction "2_2") (pintype "input"))
    )
    (net (code "51") (name "Net-(LED8-A)") (class "Default")
      (node (ref "LED8") (pin "2") (pinfunction "A_2") (pintype "input"))
      (node (ref "R45") (pin "1") (pinfunction "1_1") (pintype "input"))
    )
    (net (code "52") (name "Net-(Q1-B)") (class "Default")
      (node (ref "Q1") (pin "1") (pinfunction "B_1") (pintype "input"))
      (node (ref "R44") (pin "2") (pinfunction "2_2") (pintype "input"))
    )
    (net (code "53") (name "Net-(R36-Pad2)") (class "Default")
      (node (ref "R36") (pin "2") (pinfunction "2_2") (pintype "input"))
      (node (ref "SW3") (pin "1") (pinfunction "1_1") (pintype "input"))
    )
    (net (code "54") (name "Net-(R38-Pad1)") (class "Default")
      (node (ref "R38") (pin "1") (pinfunction "1_1") (pintype "input"))
      (node (ref "SW4") (pin "1") (pinfunction "1_1") (pintype "input"))
      (node (ref "SW5") (pin "2") (pinfunction "2_2") (pintype "input"))
    )
    (net (code "55") (name "Net-(U14-BOOT)") (class "Default")
      (node (ref "C7") (pin "1") (pinfunction "1_1") (pintype "input"))
      (node (ref "U14") (pin "1") (pinfunction "BOOT_1") (pintype "unspecified"))
    )
    (net (code "56") (name "Net-(U14-VIN)") (class "Default")
      (node (ref "C10") (pin "2") (pinfunction "2_2") (pintype "unspecified"))
      (node (ref "C11") (pin "2") (pinfunction "2_2") (pintype "unspecified"))
      (node (ref "C14") (pin "2") (pinfunction "2_2") (pintype "unspecified"))
      (node (ref "R9") (pin "2") (pinfunction "2_2") (pintype "input"))
      (node (ref "SW2") (pin "2") (pinfunction "2_2") (pintype "unspecified"))
      (node (ref "U14") (pin "7") (pinfunction "VIN_7") (pintype "input"))
    )
    (net (code "57") (name "Net-(U14-VSENSE)") (class "Default")
      (node (ref "R6") (pin "1") (pinfunction "1_1") (pintype "input"))
      (node (ref "R7") (pin "2") (pinfunction "2_2") (pintype "input"))
      (node (ref "U14") (pin "4") (pinfunction "VSENSE_4") (pintype "output"))
    )
    (net (code "58") (name "Net-(U31-FB)") (class "Default")
      (node (ref "R41") (pin "2") (pinfunction "2_2") (pintype "input"))
      (node (ref "R42") (pin "1") (pinfunction "1_1") (pintype "input"))
      (node (ref "U31") (pin "3") (pinfunction "FB_3") (pintype "unspecified"))
    )
    (net (code "59") (name "Net-(USB1-CC1)") (class "Default")
      (node (ref "R39") (pin "2") (pinfunction "2_2") (pintype "input"))
      (node (ref "USB1") (pin "A5") (pinfunction "CC1_A5") (pintype "unspecified"))
    )
    (net (code "60") (name "Net-(USB1-CC2)") (class "Default")
      (node (ref "R40") (pin "1") (pinfunction "1_1") (pintype "input"))
      (node (ref "USB1") (pin "B5") (pinfunction "CC2_B5") (pintype "unspecified"))
    )
    (net (code "61") (name "VCC") (class "Default")
      (node (ref "C38") (pin "2") (pinfunction "2_2") (pintype "input"))
      (node (ref "C39") (pin "2") (pinfunction "2_2") (pintype "input"))
      (node (ref "L2") (pin "1") (pinfunction "1_1") (pintype "unspecified"))
      (node (ref "U31") (pin "4") (pinfunction "EN_4") (pintype "unspecified"))
      (node (ref "U31") (pin "5") (pinfunction "VIN_5") (pintype "unspecified"))
      (node (ref "USB1") (pin "A9") (pinfunction "VBUS_A9") (pintype "unspecified"))
      (node (ref "USB1") (pin "B4") (pinfunction "VBUS_B4") (pintype "unspecified"))
    )
    (net (code "62") (name "VIN") (class "Default")
      (node (ref "BAT1") (pin "1") (pinfunction "1_1") (pintype "unspecified"))
      (node (ref "D3") (pin "1") (pinfunction "K_1") (pintype "unspecified"))
      (node (ref "R44") (pin "1") (pinfunction "1_1") (pintype "input"))
      (node (ref "SW2") (pin "3") (pinfunction "3_3") (pintype "unspecified"))
    )
    (net (code "63") (name "unconnected-(SW2-Pad1)") (class "Default")
      (node (ref "SW2") (pin "1") (pinfunction "1_1") (pintype "unspecified+no_connect"))
    )
    (net (code "64") (name "unconnected-(U14-ENA-Pad5)") (class "Default")
      (node (ref "U14") (pin "5") (pinfunction "ENA_5") (pintype "input+no_connect"))
    )
    (net (code "65") (name "unconnected-(U14-NC-Pad2)") (class "Default")
      (node (ref "U14") (pin "2") (pinfunction "NC_2") (pintype "unspecified+no_connect"))
    )
    (net (code "66") (name "unconnected-(U14-NC-Pad3)") (class "Default")
      (node (ref "U14") (pin "3") (pinfunction "NC_3") (pintype "unspecified+no_connect"))
    )
    (net (code "67") (name "unconnected-(U15-NC-Pad4)") (class "Default")
      (node (ref "U15") (pin "4") (pinfunction "NC_4") (pintype "unspecified+no_connect"))
    )
    (net (code "68") (name "unconnected-(U31-NC-Pad6)") (class "Default")
      (node (ref "U31") (pin "6") (pinfunction "NC_6") (pintype "unspecified+no_connect"))
    )
    (net (code "69") (name "unconnected-(U32-Pad5)") (class "Default")
      (node (ref "U32") (pin "5") (pinfunction "5_5") (pintype "unspecified"))
    )
    (net (code "70") (name "unconnected-(USB1-DN1-PadA7)") (class "Default")
      (node (ref "USB1") (pin "A7") (pinfunction "DN1_A7") (pintype "unspecified+no_connect"))
    )
    (net (code "71") (name "unconnected-(USB1-DN2-PadB7)") (class "Default")
      (node (ref "USB1") (pin "B7") (pinfunction "DN2_B7") (pintype "unspecified+no_connect"))
    )
    (net (code "72") (name "unconnected-(USB1-DP1-PadA6)") (class "Default")
      (node (ref "USB1") (pin "A6") (pinfunction "DP1_A6") (pintype "unspecified+no_connect"))
    )
    (net (code "73") (name "unconnected-(USB1-DP2-PadB6)") (class "Default")
      (node (ref "USB1") (pin "B6") (pinfunction "DP2_B6") (pintype "unspecified+no_connect"))
    )
    (net (code "74") (name "unconnected-(USB1-EP-Pad1)") (class "Default")
      (node (ref "USB1") (pin "1") (pinfunction "EP_1") (pintype "unspecified+no_connect"))
    )
    (net (code "75") (name "unconnected-(USB1-EP-Pad2)") (class "Default")
      (node (ref "USB1") (pin "2") (pinfunction "EP_2") (pintype "unspecified+no_connect"))
    )
    (net (code "76") (name "unconnected-(USB1-EP-Pad3)") (class "Default")
      (node (ref "USB1") (pin "3") (pinfunction "EP_3") (pintype "unspecified+no_connect"))
    )
    (net (code "77") (name "unconnected-(USB1-EP-Pad4)") (class "Default")
      (node (ref "USB1") (pin "4") (pinfunction "EP_4") (pintype "unspecified+no_connect"))
    )
    (net (code "78") (name "unconnected-(USB1-SSRXn1-PadB10)") (class "Default")
      (node (ref "USB1") (pin "B10") (pinfunction "SSRXn1_B10") (pintype "unspecified+no_connect"))
    )
    (net (code "79") (name "unconnected-(USB1-SSRXn2-PadA10)") (class "Default")
      (node (ref "USB1") (pin "A10") (pinfunction "SSRXn2_A10") (pintype "unspecified+no_connect"))
    )
    (net (code "80") (name "unconnected-(USB1-SSRXp1-PadB11)") (class "Default")
      (node (ref "USB1") (pin "B11") (pinfunction "SSRXp1_B11") (pintype "unspecified+no_connect"))
    )
    (net (code "81") (name "unconnected-(USB1-SSRXp2-PadA11)") (class "Default")
      (node (ref "USB1") (pin "A11") (pinfunction "SSRXp2_A11") (pintype "unspecified+no_connect"))
    )
    (net (code "82") (name "unconnected-(USB1-SSTXP1-PadA2)") (class "Default")
      (node (ref "USB1") (pin "A2") (pinfunction "SSTXP1_A2") (pintype "unspecified+no_connect"))
    )
    (net (code "83") (name "unconnected-(USB1-SSTXn1-PadA3)") (class "Default")
      (node (ref "USB1") (pin "A3") (pinfunction "SSTXn1_A3") (pintype "unspecified+no_connect"))
    )
    (net (code "84") (name "unconnected-(USB1-SSTXn2-PadB3)") (class "Default")
      (node (ref "USB1") (pin "B3") (pinfunction "SSTXn2_B3") (pintype "unspecified+no_connect"))
    )
    (net (code "85") (name "unconnected-(USB1-SSTXp2-PadB2)") (class "Default")
      (node (ref "USB1") (pin "B2") (pinfunction "SSTXp2_B2") (pintype "unspecified+no_connect"))
    )
    (net (code "86") (name "unconnected-(USB1-SUB1-PadA8)") (class "Default")
      (node (ref "USB1") (pin "A8") (pinfunction "SUB1_A8") (pintype "unspecified+no_connect"))
    )
    (net (code "87") (name "unconnected-(USB1-SUB2-PadB8)") (class "Default")
      (node (ref "USB1") (pin "B8") (pinfunction "SUB2_B8") (pintype "unspecified+no_connect"))
    )
    (net (code "88") (name "unconnected-(USB1-VBUS-PadA4)") (class "Default")
      (node (ref "USB1") (pin "A4") (pinfunction "VBUS_A4") (pintype "unspecified"))
    )
    (net (code "89") (name "unconnected-(USB1-VBUS-PadB9)") (class "Default")
      (node (ref "USB1") (pin "B9") (pinfunction "VBUS_B9") (pintype "unspecified"))
    )
  )
)
